# senseStack_SensorModule_schematic.net
KiCad netlist of a schematic drawn in EasyEDA
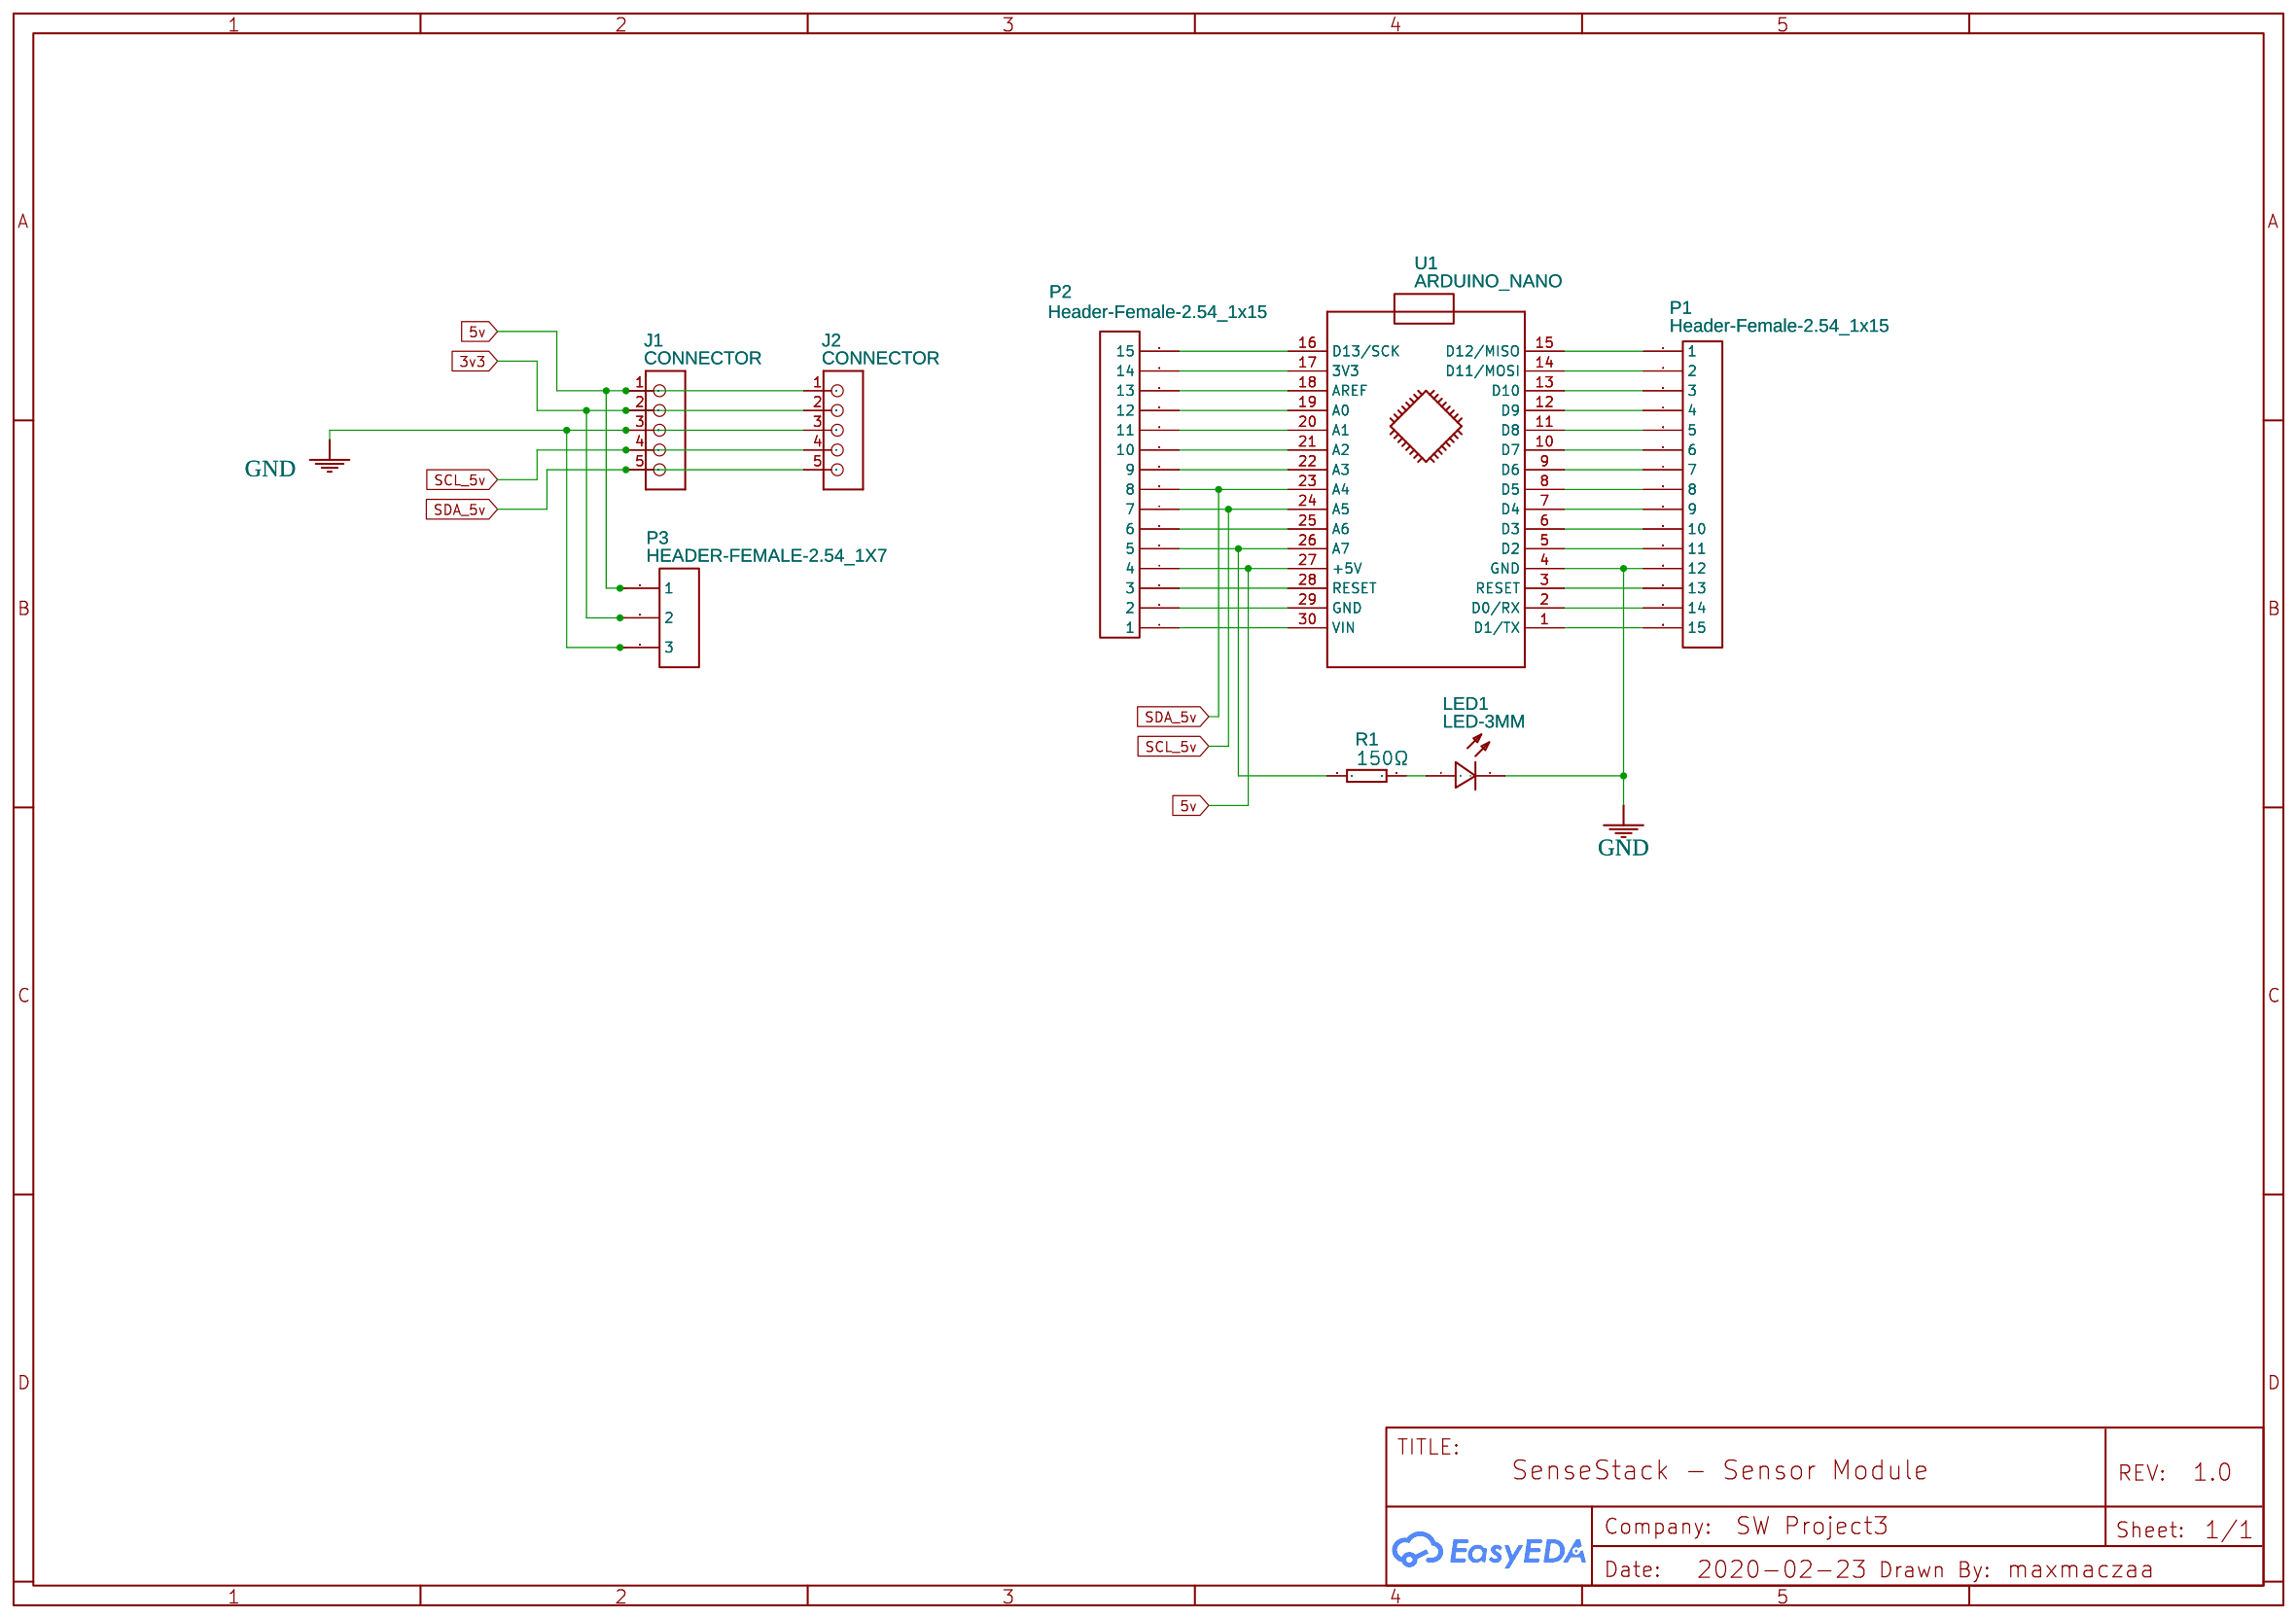
[diagram p0: schematic sheet]

(export (version "E")
  (design (tool "Eeschema 10.0.6"))
  (components
    (comp (ref "J1")
      (value "CONNECTOR")
      (libsource (lib "") (part "CONNECTOR_HEADER-6P_CONNECTOR_6P-2.54-8040MIL"))
    )
    (comp (ref "J2")
      (value "CONNECTOR")
      (libsource (lib "") (part "CONNECTOR_HEADER-6P_CONNECTOR_6P-2.54-8040MIL"))
    )
    (comp (ref "LED1")
      (value "LED-3MM")
      (fields
        (field (name "BOM_Manufacturer Part") "204-10SURD/S530-A3")
        (field (name "BOM_Supplier Part") "C99772")
      )
      (libsource (lib "") (part "LED-3MM"))
    )
    (comp (ref "P1")
      (value "Header-Female-2.54_1x15")
      (fields (field (name "BOM_Supplier Part") "undefined"))
      (libsource (lib "") (part "Header-Female-2.54_1x15"))
    )
    (comp (ref "P2")
      (value "Header-Female-2.54_1x15")
      (fields (field (name "BOM_Supplier Part") "undefined"))
      (libsource (lib "") (part "Header-Female-2.54_1x15_1"))
    )
    (comp (ref "P3")
      (value "HEADER-FEMALE-2.54_1X7")
      (fields
        (field (name "BOM_Manufacturer Part") "Header-Female-2.54_1x10")
        (field (name "BOM_Supplier Part") "undefined")
      )
      (libsource (lib "") (part "HEADER-FEMALE-2.54_1X7"))
    )
    (comp (ref "R1") (value "150Ω") (libsource (lib "") (part "RESISTOR")))
    (comp (ref "U1") (value "ARDUINO_NANO") (libsource (lib "") (part "ARDUINO_NANO")))
  )
  (nets
    (net (code "1") (name "3v3") (class "Default")
      (node (ref "J1") (pin "2") (pinfunction "2_2") (pintype "unspecified"))
      (node (ref "J2") (pin "2") (pinfunction "2_2") (pintype "unspecified"))
      (node (ref "P3") (pin "2") (pinfunction "2_2") (pintype "input"))
    )
    (net (code "2") (name "5v") (class "Default")
      (node (ref "J1") (pin "1") (pinfunction "1_1") (pintype "unspecified"))
      (node (ref "J2") (pin "1") (pinfunction "1_1") (pintype "unspecified"))
      (node (ref "P2") (pin "4") (pinfunction "4_4") (pintype "input"))
      (node (ref "P3") (pin "1") (pinfunction "1_1") (pintype "input"))
      (node (ref "U1") (pin "27") (pinfunction "+5V_27") (pintype "unspecified"))
    )
    (net (code "3") (name "GND") (class "Default")
      (node (ref "J1") (pin "3") (pinfunction "3_3") (pintype "unspecified"))
      (node (ref "J2") (pin "3") (pinfunction "3_3") (pintype "unspecified"))
      (node (ref "LED1") (pin "2") (pinfunction "-_2") (pintype "unspecified"))
      (node (ref "P1") (pin "12") (pinfunction "12_12") (pintype "input"))
      (node (ref "P3") (pin "3") (pinfunction "3_3") (pintype "input"))
      (node (ref "U1") (pin "4") (pinfunction "GND_4") (pintype "unspecified"))
    )
    (net (code "4") (name "Net-(LED1-+)") (class "Default")
      (node (ref "LED1") (pin "1") (pinfunction "+_1") (pintype "unspecified"))
      (node (ref "R1") (pin "2") (pinfunction "2_2") (pintype "unspecified"))
    )
    (net (code "5") (name "Net-(P1-Pad13)") (class "Default")
      (node (ref "P1") (pin "13") (pinfunction "13_13") (pintype "input"))
      (node (ref "U1") (pin "3") (pinfunction "RESET_3") (pintype "unspecified"))
    )
    (net (code "6") (name "Net-(P2-Pad2)") (class "Default")
      (node (ref "P2") (pin "2") (pinfunction "2_2") (pintype "input"))
      (node (ref "U1") (pin "29") (pinfunction "GND_29") (pintype "unspecified"))
    )
    (net (code "7") (name "Net-(P2-Pad3)") (class "Default")
      (node (ref "P2") (pin "3") (pinfunction "3_3") (pintype "input"))
      (node (ref "U1") (pin "28") (pinfunction "RESET_28") (pintype "unspecified"))
    )
    (net (code "8") (name "Net-(U1-3V3)") (class "Default")
      (node (ref "P2") (pin "14") (pinfunction "14_14") (pintype "input"))
      (node (ref "U1") (pin "17") (pinfunction "3V3_17") (pintype "unspecified"))
    )
    (net (code "9") (name "Net-(U1-A0)") (class "Default")
      (node (ref "P2") (pin "12") (pinfunction "12_12") (pintype "input"))
      (node (ref "U1") (pin "19") (pinfunction "A0_19") (pintype "unspecified"))
    )
    (net (code "10") (name "Net-(U1-A1)") (class "Default")
      (node (ref "P2") (pin "11") (pinfunction "11_11") (pintype "input"))
      (node (ref "U1") (pin "20") (pinfunction "A1_20") (pintype "unspecified"))
    )
    (net (code "11") (name "Net-(U1-A2)") (class "Default")
      (node (ref "P2") (pin "10") (pinfunction "10_10") (pintype "input"))
      (node (ref "U1") (pin "21") (pinfunction "A2_21") (pintype "unspecified"))
    )
    (net (code "12") (name "Net-(U1-A3)") (class "Default")
      (node (ref "P2") (pin "9") (pinfunction "9_9") (pintype "input"))
      (node (ref "U1") (pin "22") (pinfunction "A3_22") (pintype "unspecified"))
    )
    (net (code "13") (name "Net-(U1-A6)") (class "Default")
      (node (ref "P2") (pin "6") (pinfunction "6_6") (pintype "input"))
      (node (ref "U1") (pin "25") (pinfunction "A6_25") (pintype "unspecified"))
    )
    (net (code "14") (name "Net-(U1-A7)") (class "Default")
      (node (ref "P2") (pin "5") (pinfunction "5_5") (pintype "input"))
      (node (ref "R1") (pin "1") (pinfunction "1_1") (pintype "unspecified"))
      (node (ref "U1") (pin "26") (pinfunction "A7_26") (pintype "unspecified"))
    )
    (net (code "15") (name "Net-(U1-AREF)") (class "Default")
      (node (ref "P2") (pin "13") (pinfunction "13_13") (pintype "input"))
      (node (ref "U1") (pin "18") (pinfunction "AREF_18") (pintype "unspecified"))
    )
    (net (code "16") (name "Net-(U1-D0{slash}RX)") (class "Default")
      (node (ref "P1") (pin "14") (pinfunction "14_14") (pintype "input"))
      (node (ref "U1") (pin "2") (pinfunction "D0/RX_2") (pintype "unspecified"))
    )
    (net (code "17") (name "Net-(U1-D1{slash}TX)") (class "Default")
      (node (ref "P1") (pin "15") (pinfunction "15_15") (pintype "input"))
      (node (ref "U1") (pin "1") (pinfunction "D1/TX_1") (pintype "unspecified"))
    )
    (net (code "18") (name "Net-(U1-D2)") (class "Default")
      (node (ref "P1") (pin "11") (pinfunction "11_11") (pintype "input"))
      (node (ref "U1") (pin "5") (pinfunction "D2_5") (pintype "unspecified"))
    )
    (net (code "19") (name "Net-(U1-D3)") (class "Default")
      (node (ref "P1") (pin "10") (pinfunction "10_10") (pintype "input"))
      (node (ref "U1") (pin "6") (pinfunction "D3_6") (pintype "unspecified"))
    )
    (net (code "20") (name "Net-(U1-D4)") (class "Default")
      (node (ref "P1") (pin "9") (pinfunction "9_9") (pintype "input"))
      (node (ref "U1") (pin "7") (pinfunction "D4_7") (pintype "unspecified"))
    )
    (net (code "21") (name "Net-(U1-D5)") (class "Default")
      (node (ref "P1") (pin "8") (pinfunction "8_8") (pintype "input"))
      (node (ref "U1") (pin "8") (pinfunction "D5_8") (pintype "unspecified"))
    )
    (net (code "22") (name "Net-(U1-D6)") (class "Default")
      (node (ref "P1") (pin "7") (pinfunction "7_7") (pintype "input"))
      (node (ref "U1") (pin "9") (pinfunction "D6_9") (pintype "unspecified"))
    )
    (net (code "23") (name "Net-(U1-D7)") (class "Default")
      (node (ref "P1") (pin "6") (pinfunction "6_6") (pintype "input"))
      (node (ref "U1") (pin "10") (pinfunction "D7_10") (pintype "unspecified"))
    )
    (net (code "24") (name "Net-(U1-D8)") (class "Default")
      (node (ref "P1") (pin "5") (pinfunction "5_5") (pintype "input"))
      (node (ref "U1") (pin "11") (pinfunction "D8_11") (pintype "unspecified"))
    )
    (net (code "25") (name "Net-(U1-D9)") (class "Default")
      (node (ref "P1") (pin "4") (pinfunction "4_4") (pintype "input"))
      (node (ref "U1") (pin "12") (pinfunction "D9_12") (pintype "unspecified"))
    )
    (net (code "26") (name "Net-(U1-D10)") (class "Default")
      (node (ref "P1") (pin "3") (pinfunction "3_3") (pintype "input"))
      (node (ref "U1") (pin "13") (pinfunction "D10_13") (pintype "unspecified"))
    )
    (net (code "27") (name "Net-(U1-D11{slash}MOSI)") (class "Default")
      (node (ref "P1") (pin "2") (pinfunction "2_2") (pintype "input"))
      (node (ref "U1") (pin "14") (pinfunction "D11/MOSI_14") (pintype "unspecified"))
    )
    (net (code "28") (name "Net-(U1-D12{slash}MISO)") (class "Default")
      (node (ref "P1") (pin "1") (pinfunction "1_1") (pintype "input"))
      (node (ref "U1") (pin "15") (pinfunction "D12/MISO_15") (pintype "unspecified"))
    )
    (net (code "29") (name "Net-(U1-D13{slash}SCK)") (class "Default")
      (node (ref "P2") (pin "15") (pinfunction "15_15") (pintype "input"))
      (node (ref "U1") (pin "16") (pinfunction "D13/SCK_16") (pintype "unspecified"))
    )
    (net (code "30") (name "Net-(U1-VIN)") (class "Default")
      (node (ref "P2") (pin "1") (pinfunction "1_1") (pintype "input"))
      (node (ref "U1") (pin "30") (pinfunction "VIN_30") (pintype "unspecified"))
    )
    (net (code "31") (name "SCL_5v") (class "Default")
      (node (ref "J1") (pin "4") (pinfunction "4_4") (pintype "unspecified"))
      (node (ref "J2") (pin "4") (pinfunction "4_4") (pintype "unspecified"))
      (node (ref "P2") (pin "7") (pinfunction "7_7") (pintype "input"))
      (node (ref "U1") (pin "24") (pinfunction "A5_24") (pintype "unspecified"))
    )
    (net (code "32") (name "SDA_5v") (class "Default")
      (node (ref "J1") (pin "5") (pinfunction "4_5") (pintype "unspecified"))
      (node (ref "J2") (pin "5") (pinfunction "4_5") (pintype "unspecified"))
      (node (ref "P2") (pin "8") (pinfunction "8_8") (pintype "input"))
      (node (ref "U1") (pin "23") (pinfunction "A4_23") (pintype "unspecified"))
    )
  )
)
